# AST1002.net
KiCad netlist of a schematic drawn in EAGLE
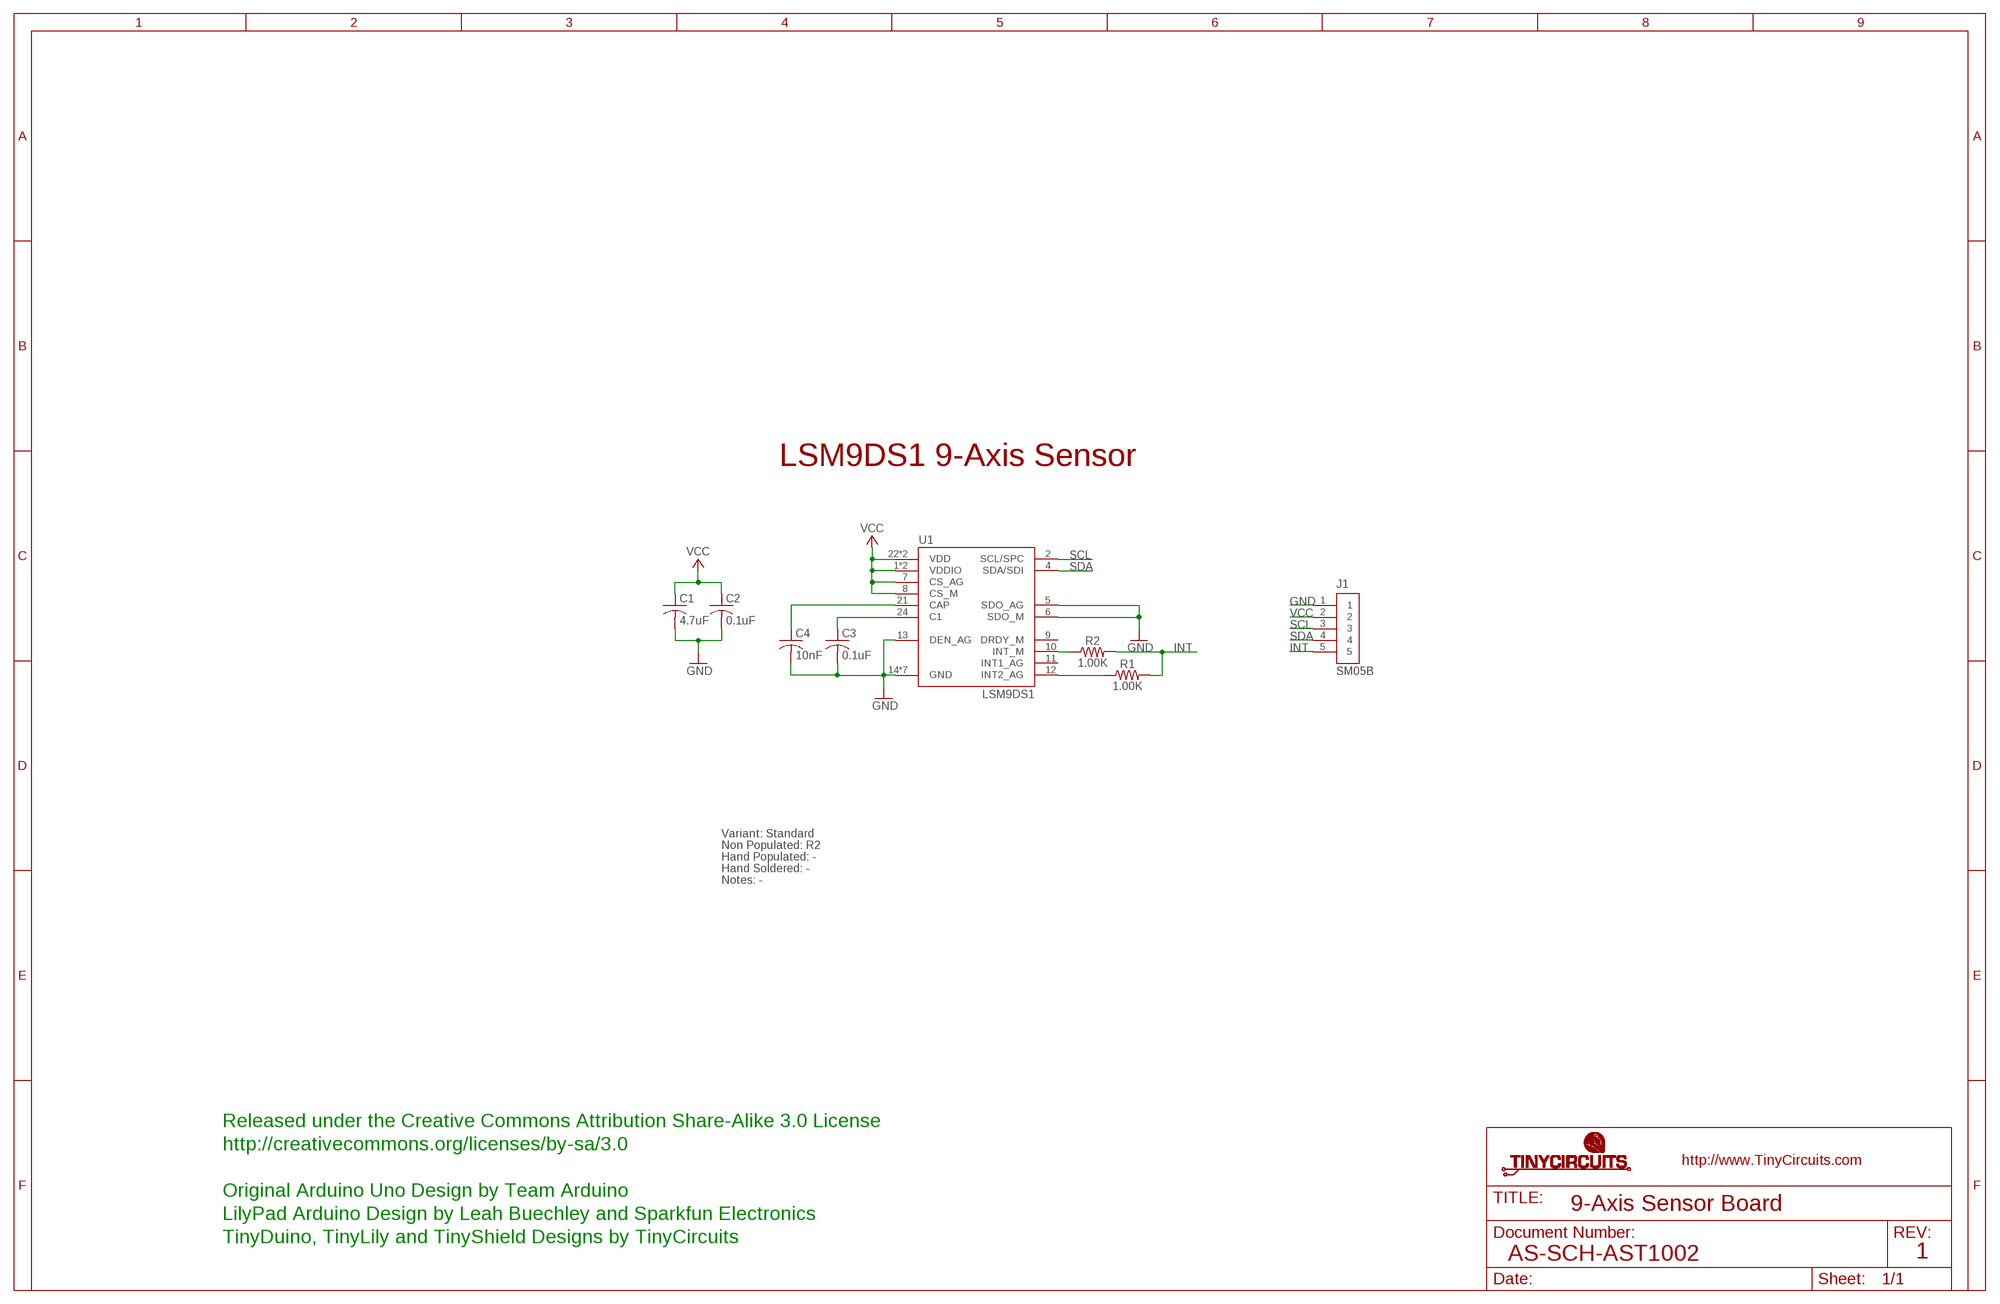
[diagram p0: schematic, sheet 1]

(export (version "E")
  (design (tool "Eeschema 10.0.6"))
  (components
    (comp (ref "C1")
      (value "4.7uF")
      (footprint "eagle-import:C0603")
      (fields (field (name "PARTNO") "AS-ITM-00088") (field (name "PARTNO_1") "AS-ITM-00088"))
      (libsource (lib "eagle-import") (part "AS-ITM-00088"))
    )
    (comp (ref "C2")
      (value "0.1uF")
      (footprint "eagle-import:C0402")
      (fields (field (name "PARTNO") "AS-ITM-00008"))
      (libsource (lib "eagle-import") (part "AS-ITM-00008"))
    )
    (comp (ref "C3")
      (value "0.1uF")
      (footprint "eagle-import:C0402")
      (fields (field (name "PARTNO") "AS-ITM-00008") (field (name "PARTNO_1") "AS-ITM-00008"))
      (libsource (lib "eagle-import") (part "AS-ITM-00008"))
    )
    (comp (ref "C4")
      (value "10nF")
      (footprint "eagle-import:C0402")
      (fields (field (name "PARTNO") "AS-ITM-00084"))
      (libsource (lib "eagle-import") (part "AS-ITM-00084"))
    )
    (comp (ref "J1")
      (value "SM05B")
      (footprint "eagle-import:JST_SH_5X1_EDGE")
      (fields (field (name "PARTNO") "AS-ITM-00340"))
      (libsource (lib "eagle-import") (part "AS-ITM-00340EDGE"))
    )
    (comp (ref "R1")
      (value "1.00K")
      (footprint "eagle-import:0402")
      (fields (field (name "PARTNO") "AS-ITM-00003") (field (name "PARTNO_1") "AS-ITM-00003"))
      (libsource (lib "eagle-import") (part "AS-ITM-00003"))
    )
    (comp (ref "R2")
      (value "1.00K")
      (footprint "eagle-import:0402")
      (fields (field (name "PARTNO") "AS-ITM-00003") (field (name "PARTNO_1") "AS-ITM-00003"))
      (libsource (lib "eagle-import") (part "AS-ITM-00003"))
    )
    (comp (ref "U1")
      (value "LSM9DS1")
      (footprint "eagle-import:LGA-24")
      (fields (field (name "PARTNO") "AS-ITM-00265"))
      (libsource (lib "eagle-import") (part "AS-ITM-00265"))
    )
  )
  (nets
    (net (code "1") (name "/INT") (class "Default")
      (node (ref "J1") (pin "5") (pinfunction "5_5") (pintype "bidirectional"))
      (node (ref "R1") (pin "2") (pinfunction "2_2") (pintype "passive"))
      (node (ref "R2") (pin "2") (pinfunction "2_2") (pintype "passive"))
    )
    (net (code "2") (name "/SCL") (class "Default")
      (node (ref "J1") (pin "3") (pinfunction "3_3") (pintype "bidirectional"))
      (node (ref "U1") (pin "2") (pinfunction "SCL/SPC_2") (pintype "bidirectional"))
    )
    (net (code "3") (name "/SDA") (class "Default")
      (node (ref "J1") (pin "4") (pinfunction "4_4") (pintype "bidirectional"))
      (node (ref "U1") (pin "4") (pinfunction "SDA/SDI_4") (pintype "bidirectional"))
    )
    (net (code "4") (name "GND") (class "Default")
      (node (ref "C1") (pin "2") (pinfunction "2_2") (pintype "passive"))
      (node (ref "C2") (pin "2") (pinfunction "2_2") (pintype "passive"))
      (node (ref "C3") (pin "2") (pinfunction "2_2") (pintype "passive"))
      (node (ref "C4") (pin "2") (pinfunction "2_2") (pintype "passive"))
      (node (ref "J1") (pin "1") (pinfunction "1_1") (pintype "bidirectional"))
      (node (ref "U1") (pin "13") (pinfunction "DEN_AG_13") (pintype "bidirectional"))
      (node (ref "U1") (pin "14") (pinfunction "GND_14") (pintype "bidirectional"))
      (node (ref "U1") (pin "15") (pinfunction "GND_15") (pintype "bidirectional"))
      (node (ref "U1") (pin "16") (pinfunction "GND_16") (pintype "bidirectional"))
      (node (ref "U1") (pin "17") (pinfunction "GND_17") (pintype "bidirectional"))
      (node (ref "U1") (pin "18") (pinfunction "GND_18") (pintype "bidirectional"))
      (node (ref "U1") (pin "19") (pinfunction "GND_19") (pintype "bidirectional"))
      (node (ref "U1") (pin "20") (pinfunction "GND_20") (pintype "bidirectional"))
      (node (ref "U1") (pin "5") (pinfunction "SDO_AG_5") (pintype "bidirectional"))
      (node (ref "U1") (pin "6") (pinfunction "SDO_M_6") (pintype "bidirectional"))
    )
    (net (code "5") (name "Net-(U1-C1)") (class "Default")
      (node (ref "C3") (pin "1") (pinfunction "1_1") (pintype "passive"))
      (node (ref "U1") (pin "24") (pinfunction "C1_24") (pintype "bidirectional"))
    )
    (net (code "6") (name "Net-(U1-CAP)") (class "Default")
      (node (ref "C4") (pin "1") (pinfunction "1_1") (pintype "passive"))
      (node (ref "U1") (pin "21") (pinfunction "CAP_21") (pintype "bidirectional"))
    )
    (net (code "7") (name "Net-(U1-INT2_AG)") (class "Default")
      (node (ref "R1") (pin "1") (pinfunction "1_1") (pintype "passive"))
      (node (ref "U1") (pin "12") (pinfunction "INT2_AG_12") (pintype "bidirectional"))
    )
    (net (code "8") (name "Net-(U1-INT_M)") (class "Default")
      (node (ref "R2") (pin "1") (pinfunction "1_1") (pintype "passive"))
      (node (ref "U1") (pin "10") (pinfunction "INT_M_10") (pintype "bidirectional"))
    )
    (net (code "9") (name "VCC") (class "Default")
      (node (ref "C1") (pin "1") (pinfunction "1_1") (pintype "passive"))
      (node (ref "C2") (pin "1") (pinfunction "1_1") (pintype "passive"))
      (node (ref "J1") (pin "2") (pinfunction "2_2") (pintype "bidirectional"))
      (node (ref "U1") (pin "1") (pinfunction "VDDIO_1") (pintype "bidirectional"))
      (node (ref "U1") (pin "22") (pinfunction "VDD_22") (pintype "bidirectional"))
      (node (ref "U1") (pin "23") (pinfunction "VDD_23") (pintype "bidirectional"))
      (node (ref "U1") (pin "3") (pinfunction "VDDIO_3") (pintype "bidirectional"))
      (node (ref "U1") (pin "7") (pinfunction "CS_AG_7") (pintype "bidirectional"))
      (node (ref "U1") (pin "8") (pinfunction "CS_M_8") (pintype "bidirectional"))
    )
    (net (code "10") (name "unconnected-(U1-DRDY_M-Pad9)") (class "Default")
      (node (ref "U1") (pin "9") (pinfunction "DRDY_M_9") (pintype "bidirectional"))
    )
    (net (code "11") (name "unconnected-(U1-INT1_AG-Pad11)") (class "Default")
      (node (ref "U1") (pin "11") (pinfunction "INT1_AG_11") (pintype "bidirectional"))
    )
  )
)
